# gps_locator.net
KiCad netlist of a schematic drawn in EAGLE
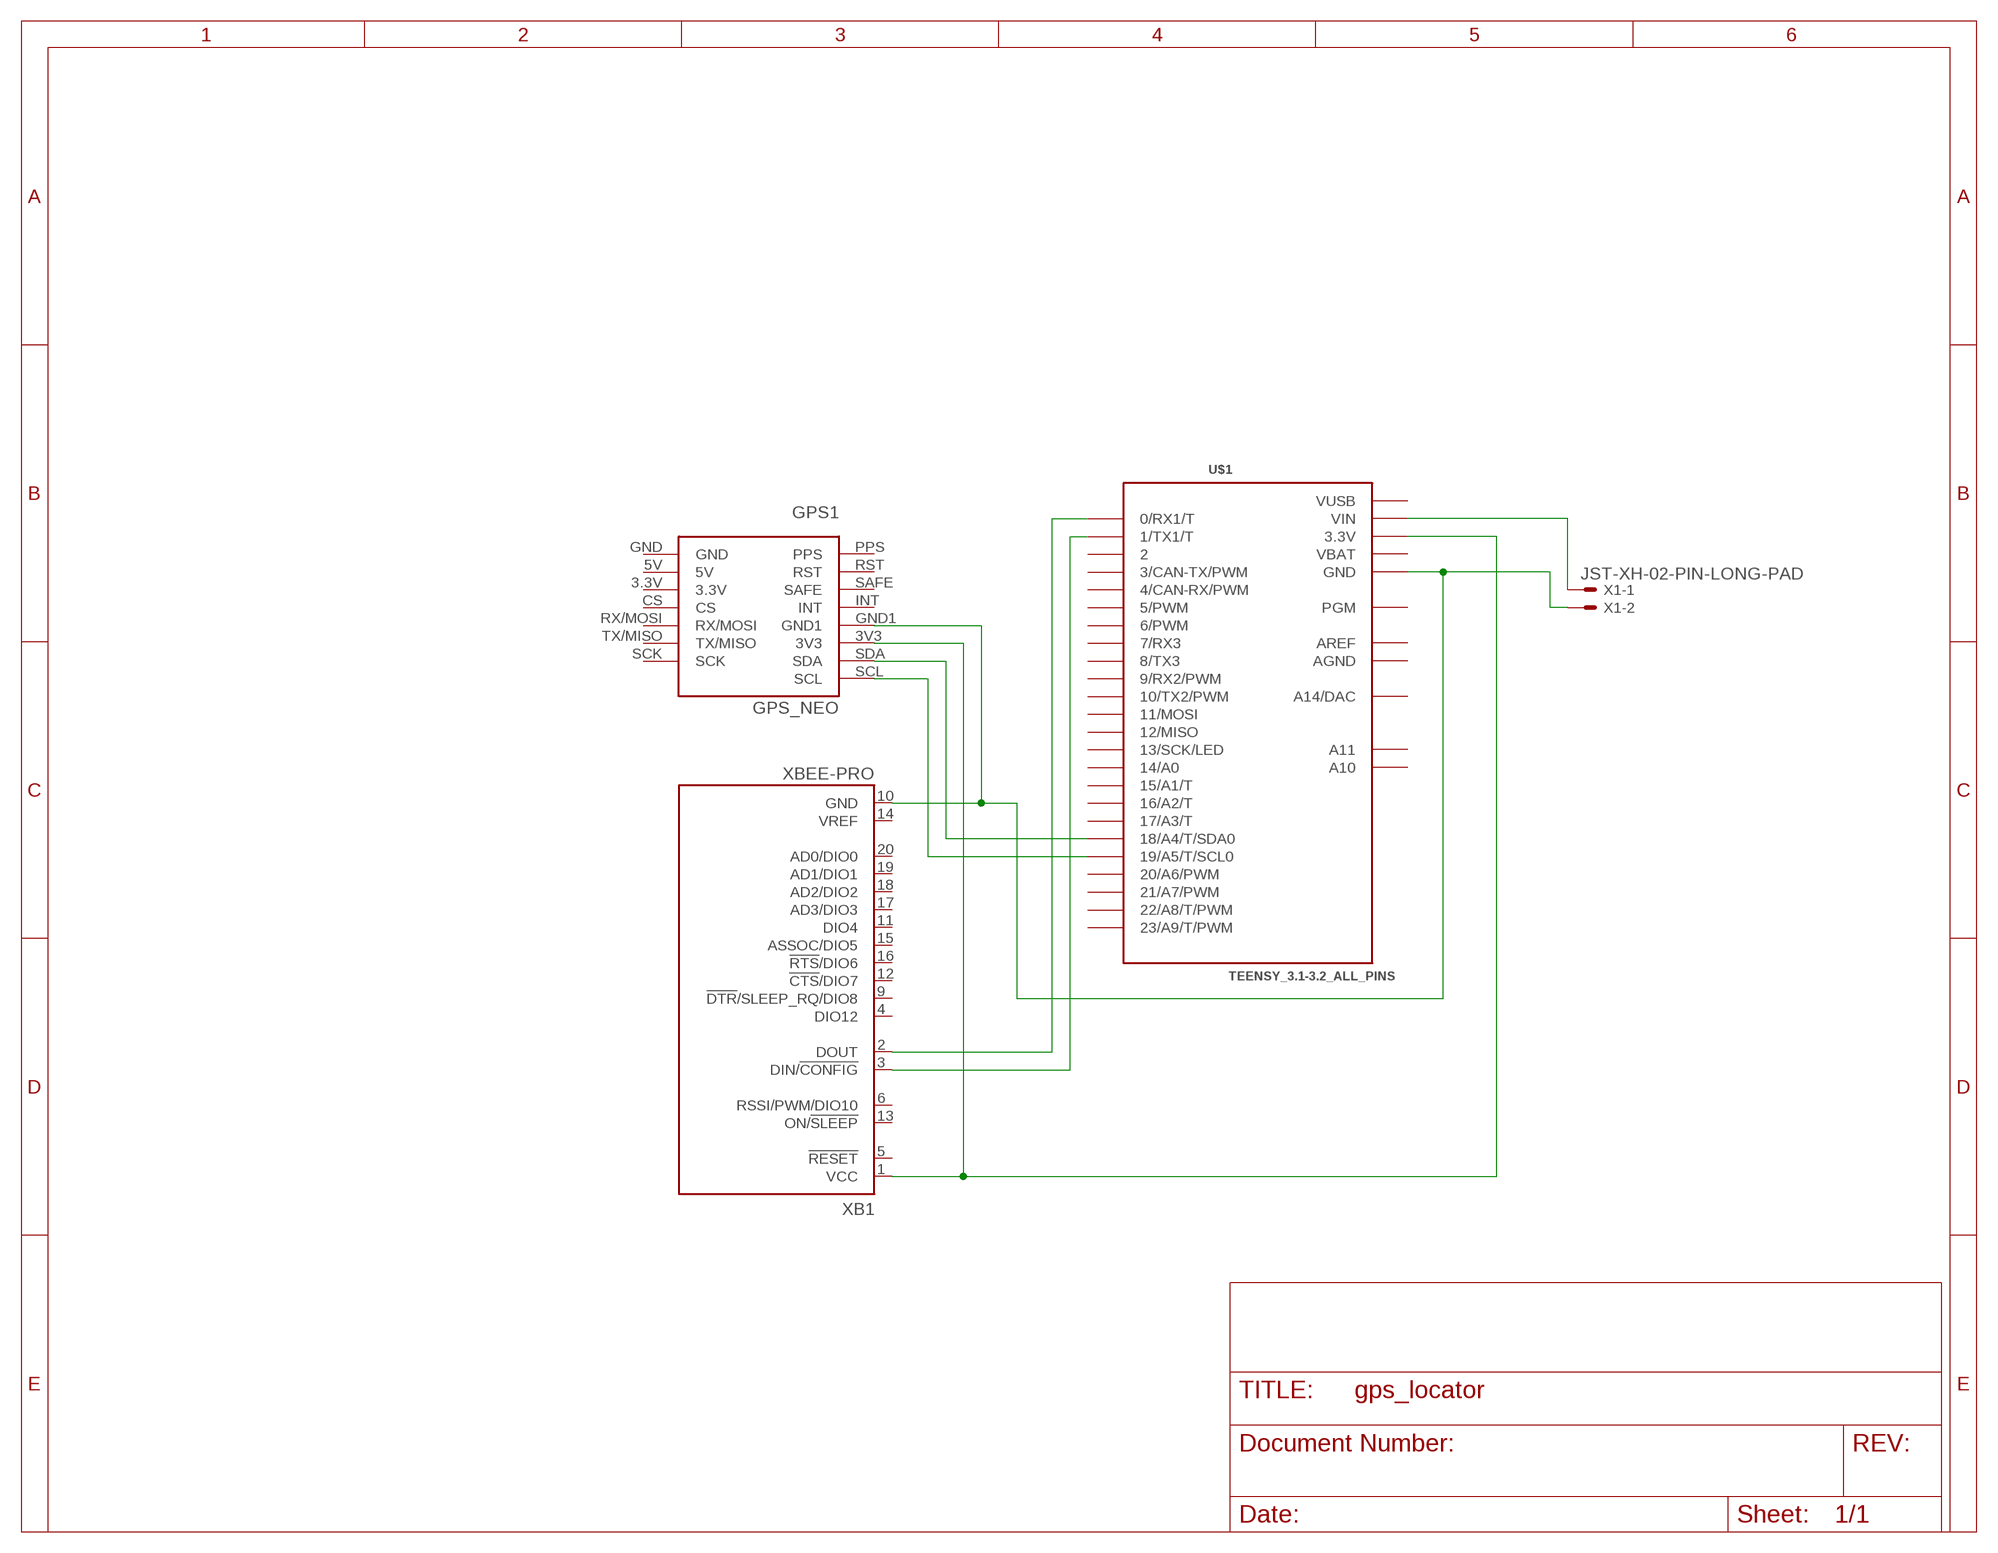
[diagram p0: schematic, sheet 1]

(export (version "E")
  (design (tool "Eeschema 10.0.6"))
  (components
    (comp (ref "GPS1")
      (value "GPS_NEO")
      (footprint "eagle-import:GPS_NEO")
      (libsource (lib "eagle-import") (part "GPS_NEO"))
    )
    (comp (ref "U$1")
      (value "TEENSY_3.1-3.2_ALL_PINS")
      (footprint "eagle-import:TEENSY_3.0-3.2&LC_ALL_PINS")
      (libsource (lib "eagle-import") (part "TEENSY_3.1-3.2_ALL_PINS"))
    )
    (comp (ref "X1")
      (value "JST-XH-02-PIN-LONG-PAD")
      (footprint "eagle-import:JST-XH-02-PACKAGE-LONG-PAD")
      (libsource (lib "eagle-import") (part "JST-XH-02-PIN-LONG-PAD"))
    )
    (comp (ref "XB1")
      (value "XBEE-PRO")
      (footprint "eagle-import:XBEE-PRO")
      (fields (field (name "MPN") "XBP24-AWI-001"))
      (libsource (lib "eagle-import") (part "XBEE-PRO"))
    )
  )
  (nets
    (net (code "1") (name "/AGND") (class "Default")
      (node (ref "U$1") (pin "AGND") (pinfunction "AGND_AGND") (pintype "power_in"))
    )
    (net (code "2") (name "/AREF") (class "Default")
      (node (ref "U$1") (pin "AREF") (pinfunction "AREF_AREF") (pintype "power_in"))
    )
    (net (code "3") (name "/VBAT") (class "Default")
      (node (ref "U$1") (pin "VBAT") (pinfunction "VBAT_VBAT") (pintype "power_in"))
    )
    (net (code "4") (name "/VUSB") (class "Default")
      (node (ref "U$1") (pin "VUSB") (pinfunction "VUSB_VUSB") (pintype "power_in"))
    )
    (net (code "5") (name "Net-(U$1-0{slash}RX1{slash}T)") (class "Default")
      (node (ref "U$1") (pin "0") (pinfunction "0/RX1/T_0") (pintype "bidirectional"))
      (node (ref "XB1") (pin "2") (pinfunction "DOUT_2") (pintype "output"))
    )
    (net (code "6") (name "Net-(U$1-1{slash}TX1{slash}T)") (class "Default")
      (node (ref "U$1") (pin "1") (pinfunction "1/TX1/T_1") (pintype "bidirectional"))
      (node (ref "XB1") (pin "3") (pinfunction "DIN/~{CONFIG}_3") (pintype "input"))
    )
    (net (code "7") (name "Net-(U$1-18{slash}A4{slash}T{slash}SDA0)") (class "Default")
      (node (ref "GPS1") (pin "SDA") (pinfunction "SDA_SDA") (pintype "bidirectional"))
      (node (ref "U$1") (pin "18/A4") (pinfunction "18/A4/T/SDA0_18/A4") (pintype "bidirectional"))
    )
    (net (code "8") (name "Net-(U$1-19{slash}A5{slash}T{slash}SCL0)") (class "Default")
      (node (ref "GPS1") (pin "SCL") (pinfunction "SCL_SCL") (pintype "bidirectional"))
      (node (ref "U$1") (pin "19/A5") (pinfunction "19/A5/T/SCL0_19/A5") (pintype "bidirectional"))
    )
    (net (code "9") (name "Net-(X1A-S)") (class "Default")
      (node (ref "U$1") (pin "VIN") (pinfunction "VIN_VIN") (pintype "power_in"))
      (node (ref "X1") (pin "1") (pinfunction "S_1") (pintype "passive"))
    )
    (net (code "10") (name "Net-(X1B-S)") (class "Default")
      (node (ref "GPS1") (pin "GND1") (pinfunction "GND1_GND1") (pintype "bidirectional"))
      (node (ref "U$1") (pin "GND") (pinfunction "GND_GND") (pintype "power_in"))
      (node (ref "U$1") (pin "GND1") (pinfunction "GND_GND1") (pintype "power_in"))
      (node (ref "X1") (pin "2") (pinfunction "S_2") (pintype "passive"))
      (node (ref "XB1") (pin "10") (pinfunction "GND_10") (pintype "power_in"))
    )
    (net (code "11") (name "Net-(XB1-VCC)") (class "Default")
      (node (ref "GPS1") (pin "3V3") (pinfunction "3V3_3V3") (pintype "bidirectional"))
      (node (ref "U$1") (pin "3.3V") (pinfunction "3.3V_3.3V") (pintype "power_in"))
      (node (ref "U$1") (pin "3.3V1") (pinfunction "3.3V_3.3V1") (pintype "power_in"))
      (node (ref "XB1") (pin "1") (pinfunction "VCC_1") (pintype "power_in"))
    )
    (net (code "12") (name "unconnected-(GPS1-Pad3.3V)") (class "Default")
      (node (ref "GPS1") (pin "3.3V") (pinfunction "3.3V_3.3V") (pintype "bidirectional"))
    )
    (net (code "13") (name "unconnected-(GPS1-Pad5V)") (class "Default")
      (node (ref "GPS1") (pin "5V") (pinfunction "5V_5V") (pintype "bidirectional"))
    )
    (net (code "14") (name "unconnected-(GPS1-PadCS)") (class "Default")
      (node (ref "GPS1") (pin "CS") (pinfunction "CS_CS") (pintype "bidirectional"))
    )
    (net (code "15") (name "unconnected-(GPS1-PadGND)") (class "Default")
      (node (ref "GPS1") (pin "GND") (pinfunction "GND_GND") (pintype "bidirectional"))
    )
    (net (code "16") (name "unconnected-(GPS1-PadINT)") (class "Default")
      (node (ref "GPS1") (pin "INT") (pinfunction "INT_INT") (pintype "bidirectional"))
    )
    (net (code "17") (name "unconnected-(GPS1-PadPPS)") (class "Default")
      (node (ref "GPS1") (pin "PPS") (pinfunction "PPS_PPS") (pintype "bidirectional"))
    )
    (net (code "18") (name "unconnected-(GPS1-PadRST)") (class "Default")
      (node (ref "GPS1") (pin "RST") (pinfunction "RST_RST") (pintype "bidirectional"))
    )
    (net (code "19") (name "unconnected-(GPS1-PadRX{slash}MOSI)") (class "Default")
      (node (ref "GPS1") (pin "RX/MOSI") (pinfunction "RX/MOSI_RX/MOSI") (pintype "bidirectional"))
    )
    (net (code "20") (name "unconnected-(GPS1-PadSAFE)") (class "Default")
      (node (ref "GPS1") (pin "SAFE") (pinfunction "SAFE_SAFE") (pintype "bidirectional"))
    )
    (net (code "21") (name "unconnected-(GPS1-PadSCK)") (class "Default")
      (node (ref "GPS1") (pin "SCK") (pinfunction "SCK_SCK") (pintype "bidirectional"))
    )
    (net (code "22") (name "unconnected-(GPS1-PadTX{slash}MISO)") (class "Default")
      (node (ref "GPS1") (pin "TX/MISO") (pinfunction "TX/MISO_TX/MISO") (pintype "bidirectional"))
    )
    (net (code "23") (name "unconnected-(U$1-3{slash}CAN-TX{slash}PWM-Pad3)") (class "Default")
      (node (ref "U$1") (pin "3") (pinfunction "3/CAN-TX/PWM_3") (pintype "bidirectional"))
    )
    (net (code "24") (name "unconnected-(U$1-4{slash}CAN-RX{slash}PWM-Pad4)") (class "Default")
      (node (ref "U$1") (pin "4") (pinfunction "4/CAN-RX/PWM_4") (pintype "bidirectional"))
    )
    (net (code "25") (name "unconnected-(U$1-5{slash}PWM-Pad5)") (class "Default")
      (node (ref "U$1") (pin "5") (pinfunction "5/PWM_5") (pintype "bidirectional"))
    )
    (net (code "26") (name "unconnected-(U$1-6{slash}PWM-Pad6)") (class "Default")
      (node (ref "U$1") (pin "6") (pinfunction "6/PWM_6") (pintype "bidirectional"))
    )
    (net (code "27") (name "unconnected-(U$1-7{slash}RX3-Pad7)") (class "Default")
      (node (ref "U$1") (pin "7") (pinfunction "7/RX3_7") (pintype "bidirectional"))
    )
    (net (code "28") (name "unconnected-(U$1-8{slash}TX3-Pad8)") (class "Default")
      (node (ref "U$1") (pin "8") (pinfunction "8/TX3_8") (pintype "bidirectional"))
    )
    (net (code "29") (name "unconnected-(U$1-9{slash}RX2{slash}PWM-Pad9)") (class "Default")
      (node (ref "U$1") (pin "9") (pinfunction "9/RX2/PWM_9") (pintype "bidirectional"))
    )
    (net (code "30") (name "unconnected-(U$1-10{slash}TX2{slash}PWM-Pad10)") (class "Default")
      (node (ref "U$1") (pin "10") (pinfunction "10/TX2/PWM_10") (pintype "bidirectional"))
    )
    (net (code "31") (name "unconnected-(U$1-11{slash}MOSI-Pad11)") (class "Default")
      (node (ref "U$1") (pin "11") (pinfunction "11/MOSI_11") (pintype "bidirectional"))
    )
    (net (code "32") (name "unconnected-(U$1-12{slash}MISO-Pad12)") (class "Default")
      (node (ref "U$1") (pin "12") (pinfunction "12/MISO_12") (pintype "bidirectional"))
    )
    (net (code "33") (name "unconnected-(U$1-13{slash}SCK{slash}LED-Pad13)") (class "Default")
      (node (ref "U$1") (pin "13") (pinfunction "13/SCK/LED_13") (pintype "bidirectional"))
    )
    (net (code "34") (name "unconnected-(U$1-15{slash}A1{slash}T-Pad15{slash}A1)") (class "Default")
      (node (ref "U$1") (pin "15/A1") (pinfunction "15/A1/T_15/A1") (pintype "bidirectional"))
    )
    (net (code "35") (name "unconnected-(U$1-16{slash}A2{slash}T-Pad16{slash}A2)") (class "Default")
      (node (ref "U$1") (pin "16/A2") (pinfunction "16/A2/T_16/A2") (pintype "bidirectional"))
    )
    (net (code "36") (name "unconnected-(U$1-17{slash}A3{slash}T-Pad17{slash}A3)") (class "Default")
      (node (ref "U$1") (pin "17/A3") (pinfunction "17/A3/T_17/A3") (pintype "bidirectional"))
    )
    (net (code "37") (name "unconnected-(U$1-20{slash}A6{slash}PWM-Pad20{slash}A6)") (class "Default")
      (node (ref "U$1") (pin "20/A6") (pinfunction "20/A6/PWM_20/A6") (pintype "bidirectional"))
    )
    (net (code "38") (name "unconnected-(U$1-21{slash}A7{slash}PWM-Pad21{slash}A7)") (class "Default")
      (node (ref "U$1") (pin "21/A7") (pinfunction "21/A7/PWM_21/A7") (pintype "bidirectional"))
    )
    (net (code "39") (name "unconnected-(U$1-22{slash}A8{slash}T{slash}PWM-Pad22{slash}A8)") (class "Default")
      (node (ref "U$1") (pin "22/A8") (pinfunction "22/A8/T/PWM_22/A8") (pintype "bidirectional"))
    )
    (net (code "40") (name "unconnected-(U$1-23{slash}A9{slash}T{slash}PWM-Pad23{slash}A9)") (class "Default")
      (node (ref "U$1") (pin "23/A9") (pinfunction "23/A9/T/PWM_23/A9") (pintype "bidirectional"))
    )
    (net (code "41") (name "unconnected-(U$1-A14{slash}DAC-PadRESET{slash}DAC)") (class "Default")
      (node (ref "U$1") (pin "RESET/DAC") (pinfunction "A14/DAC_RESET/DAC") (pintype "bidirectional"))
    )
    (net (code "42") (name "unconnected-(U$1-Pad2)") (class "Default")
      (node (ref "U$1") (pin "2") (pinfunction "2_2") (pintype "bidirectional"))
    )
    (net (code "43") (name "unconnected-(U$1-Pad14{slash}A0)") (class "Default")
      (node (ref "U$1") (pin "14/A0") (pinfunction "14/A0_14/A0") (pintype "bidirectional"))
    )
    (net (code "44") (name "unconnected-(U$1-PadA10)") (class "Default")
      (node (ref "U$1") (pin "A10") (pinfunction "A10_A10") (pintype "bidirectional"))
    )
    (net (code "45") (name "unconnected-(U$1-PadA11)") (class "Default")
      (node (ref "U$1") (pin "A11") (pinfunction "A11_A11") (pintype "bidirectional"))
    )
    (net (code "46") (name "unconnected-(U$1-PadPGM)") (class "Default")
      (node (ref "U$1") (pin "PGM") (pinfunction "PGM_PGM") (pintype "bidirectional"))
    )
    (net (code "47") (name "unconnected-(XB1-AD0{slash}DIO0-Pad20)") (class "Default")
      (node (ref "XB1") (pin "20") (pinfunction "AD0/DIO0_20") (pintype "bidirectional"))
    )
    (net (code "48") (name "unconnected-(XB1-AD1{slash}DIO1-Pad19)") (class "Default")
      (node (ref "XB1") (pin "19") (pinfunction "AD1/DIO1_19") (pintype "bidirectional"))
    )
    (net (code "49") (name "unconnected-(XB1-AD2{slash}DIO2-Pad18)") (class "Default")
      (node (ref "XB1") (pin "18") (pinfunction "AD2/DIO2_18") (pintype "bidirectional"))
    )
    (net (code "50") (name "unconnected-(XB1-AD3{slash}DIO3-Pad17)") (class "Default")
      (node (ref "XB1") (pin "17") (pinfunction "AD3/DIO3_17") (pintype "bidirectional"))
    )
    (net (code "51") (name "unconnected-(XB1-ASSOC{slash}DIO5-Pad15)") (class "Default")
      (node (ref "XB1") (pin "15") (pinfunction "ASSOC/DIO5_15") (pintype "bidirectional"))
    )
    (net (code "52") (name "unconnected-(XB1-DIO4-Pad11)") (class "Default")
      (node (ref "XB1") (pin "11") (pinfunction "DIO4_11") (pintype "bidirectional"))
    )
    (net (code "53") (name "unconnected-(XB1-DIO12-Pad4)") (class "Default")
      (node (ref "XB1") (pin "4") (pinfunction "DIO12_4") (pintype "bidirectional"))
    )
    (net (code "54") (name "unconnected-(XB1-ON{slash}~{SLEEP}-Pad13)") (class "Default")
      (node (ref "XB1") (pin "13") (pinfunction "ON/~{SLEEP}_13") (pintype "output"))
    )
    (net (code "55") (name "unconnected-(XB1-RSSI{slash}PWM{slash}DIO10-Pad6)") (class "Default")
      (node (ref "XB1") (pin "6") (pinfunction "RSSI/PWM/DIO10_6") (pintype "output"))
    )
    (net (code "56") (name "unconnected-(XB1-VREF-Pad14)") (class "Default")
      (node (ref "XB1") (pin "14") (pinfunction "VREF_14") (pintype "input"))
    )
    (net (code "57") (name "unconnected-(XB1-~{CTS}{slash}DIO7-Pad12)") (class "Default")
      (node (ref "XB1") (pin "12") (pinfunction "~{CTS}/DIO7_12") (pintype "bidirectional"))
    )
    (net (code "58") (name "unconnected-(XB1-~{DTR}{slash}SLEEP_RQ{slash}DIO8-Pad9)") (class "Default")
      (node (ref "XB1") (pin "9") (pinfunction "~{DTR}/SLEEP_RQ/DIO8_9") (pintype "bidirectional"))
    )
    (net (code "59") (name "unconnected-(XB1-~{RESET}-Pad5)") (class "Default")
      (node (ref "XB1") (pin "5") (pinfunction "~{RESET}_5") (pintype "input"))
    )
    (net (code "60") (name "unconnected-(XB1-~{RTS}{slash}DIO6-Pad16)") (class "Default")
      (node (ref "XB1") (pin "16") (pinfunction "~{RTS}/DIO6_16") (pintype "bidirectional"))
    )
  )
)
